# Audio-Beamformer_HMI_V1_0.net
KiCad netlist of a schematic drawn in Altium Designer
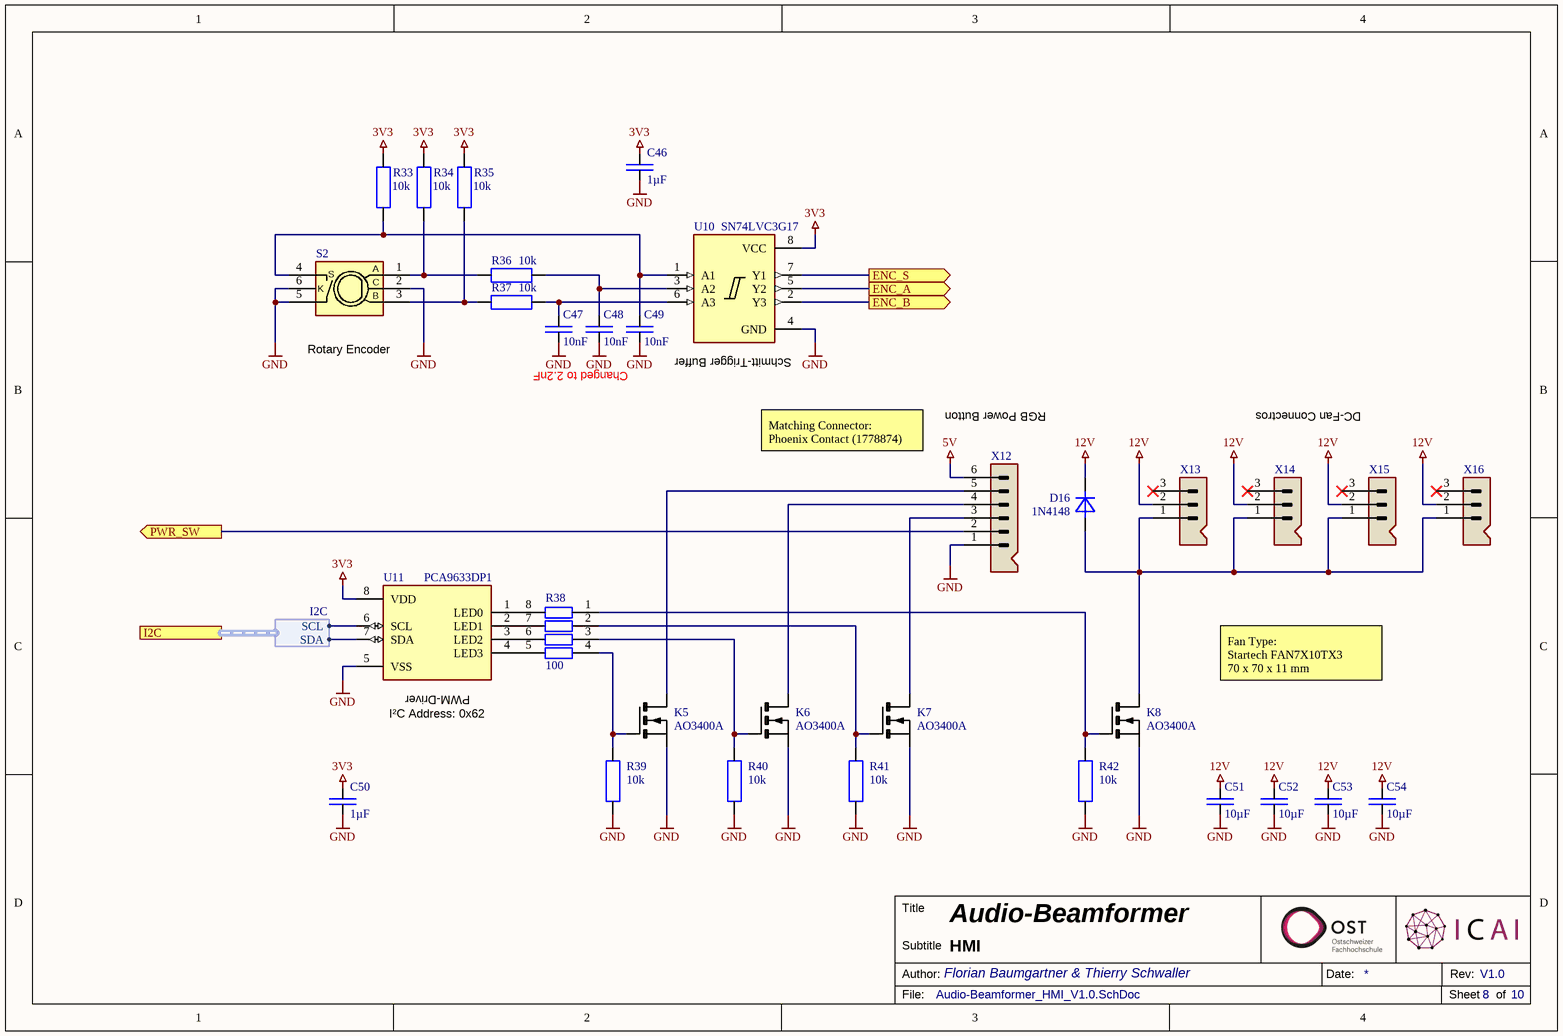
[diagram p0: Audio-Beamformer_HMI_V1.0.SchDoc]

(export (version "E")
  (design (tool "Eeschema 10.0.6"))
  (components
    (comp (ref "C46")
      (value "1µF")
      (footprint "SMD Keramikkondensator 0603")
      (description "CAP-MK")
      (libsource (lib "AudioAmp") (part "C-CAPACITOR"))
    )
    (comp (ref "C47")
      (value "10nF")
      (footprint "SMD Keramikkondensator 0603")
      (description "CAP-MK")
      (libsource (lib "AudioAmp") (part "C-CAPACITOR"))
    )
    (comp (ref "C48")
      (value "10nF")
      (footprint "SMD Keramikkondensator 0603")
      (description "CAP-MK")
      (libsource (lib "AudioAmp") (part "C-CAPACITOR"))
    )
    (comp (ref "C49")
      (value "10nF")
      (footprint "SMD Keramikkondensator 0603")
      (description "CAP-MK")
      (libsource (lib "AudioAmp") (part "C-CAPACITOR"))
    )
    (comp (ref "C50")
      (value "1µF")
      (footprint "SMD Keramikkondensator 0603")
      (description "CAP-MK")
      (libsource (lib "AudioAmp") (part "C-CAPACITOR"))
    )
    (comp (ref "C51")
      (value "10µF")
      (footprint "SMD Keramikkondensator 1206")
      (description "CAP-MK")
      (libsource (lib "AudioAmp") (part "C-CAPACITOR"))
    )
    (comp (ref "C52")
      (value "10µF")
      (footprint "SMD Keramikkondensator 1206")
      (description "CAP-MK")
      (libsource (lib "AudioAmp") (part "C-CAPACITOR"))
    )
    (comp (ref "C53")
      (value "10µF")
      (footprint "SMD Keramikkondensator 1206")
      (description "CAP-MK")
      (libsource (lib "AudioAmp") (part "C-CAPACITOR"))
    )
    (comp (ref "C54")
      (value "10µF")
      (footprint "SMD Keramikkondensator 1206")
      (description "CAP-MK")
      (libsource (lib "AudioAmp") (part "C-CAPACITOR"))
    )
    (comp (ref "D16")
      (value "1N4148")
      (footprint "SMD Diode SOD-123")
      (description "DIODE (alt V)")
      (libsource (lib "TFS Integrated Library") (part "R-DIODE"))
    )
    (comp (ref "K5")
      (value "AO3400A")
      (footprint "SMD MOSFET SOT-23")
      (description "MOSFET N-Channel")
      (libsource (lib "Nixie-Test") (part "K-FET{colon}NIGE"))
    )
    (comp (ref "K6")
      (value "AO3400A")
      (footprint "SMD MOSFET SOT-23")
      (description "MOSFET N-Channel")
      (libsource (lib "Nixie-Test") (part "K-FET{colon}NIGE"))
    )
    (comp (ref "K7")
      (value "AO3400A")
      (footprint "SMD MOSFET SOT-23")
      (description "MOSFET N-Channel")
      (libsource (lib "Nixie-Test") (part "K-FET{colon}NIGE"))
    )
    (comp (ref "K8")
      (value "AO3400A")
      (footprint "SMD MOSFET SOT-23")
      (description "MOSFET N-Channel")
      (libsource (lib "Nixie-Test") (part "K-FET{colon}NIGE"))
    )
    (comp (ref "R33")
      (value "10k")
      (footprint "SMD Widerstand 0603")
      (description "RES (E=Heizwiderstand B=Messwandler)")
      (libsource (lib "") (part "R-RESISTOR_1"))
    )
    (comp (ref "R34")
      (value "10k")
      (footprint "SMD Widerstand 0603")
      (description "RES (E=Heizwiderstand B=Messwandler)")
      (libsource (lib "") (part "R-RESISTOR_1"))
    )
    (comp (ref "R35")
      (value "10k")
      (footprint "SMD Widerstand 0603")
      (description "RES (E=Heizwiderstand B=Messwandler)")
      (libsource (lib "") (part "R-RESISTOR_1"))
    )
    (comp (ref "R36")
      (value "10k")
      (footprint "SMD Widerstand 0603")
      (description "RES (E=Heizwiderstand B=Messwandler)")
      (libsource (lib "TFS Integrated Library") (part "R-RESISTOR"))
    )
    (comp (ref "R37")
      (value "10k")
      (footprint "SMD Widerstand 0603")
      (description "RES (E=Heizwiderstand B=Messwandler)")
      (libsource (lib "TFS Integrated Library") (part "R-RESISTOR"))
    )
    (comp (ref "R38")
      (value "100")
      (footprint "SMD Widerstand Array 4-Fach 0603")
      (description "Isolated Resistor Array")
      (libsource (lib "Fleet-Monitor") (part "R-Array Single Quad E24 - 330"))
    )
    (comp (ref "R39")
      (value "10k")
      (footprint "SMD Widerstand 0603")
      (description "RES (E=Heizwiderstand B=Messwandler)")
      (libsource (lib "") (part "R-RESISTOR_1"))
    )
    (comp (ref "R40")
      (value "10k")
      (footprint "SMD Widerstand 0603")
      (description "RES (E=Heizwiderstand B=Messwandler)")
      (libsource (lib "") (part "R-RESISTOR_1"))
    )
    (comp (ref "R41")
      (value "10k")
      (footprint "SMD Widerstand 0603")
      (description "RES (E=Heizwiderstand B=Messwandler)")
      (libsource (lib "") (part "R-RESISTOR_1"))
    )
    (comp (ref "R42")
      (value "10k")
      (footprint "SMD Widerstand 0603")
      (description "RES (E=Heizwiderstand B=Messwandler)")
      (libsource (lib "") (part "R-RESISTOR_1"))
    )
    (comp (ref "S2")
      (value "PEC11R-4025F-S0024")
      (footprint "THT Rotary Encoder with Switch")
      (description "Rotary Encoder")
      (libsource (lib "Audio-Beamformer") (part "S-Rotary Encoder"))
    )
    (comp (ref "U10")
      (value "SN74LVC3G17")
      (footprint "SMD IC SM-8")
      (description "Tripple Schmitt-Trigger Buffer")
      (libsource (lib "Audio-Beamformer") (part "U-SN74LVC3G17DCTR"))
    )
    (comp (ref "U11")
      (value "PCA9633DP1")
      (footprint "SMD IC TSSOP-8")
      (description "I2C Quad LED-Driver")
      (libsource (lib "Audio-Beamformer") (part "U-PCA9633DP1"))
    )
    (comp (ref "X12")
      (value "Board-To-Wire Connector (Receptacle)")
      (footprint "THT Connector 2.5mm 6-Pol (1778667)")
      (libsource (lib "Audio-Beamformer") (part "X-Stiftleiste (6-Fach)"))
    )
    (comp (ref "X13")
      (value "Stiftleiste (3-Fach)")
      (footprint "THT Connector 2.54mm 3-Pol (61900311021)")
      (libsource (lib "Audio-Beamformer") (part "X-Stiftleiste (3-Fach)"))
    )
    (comp (ref "X14")
      (value "Stiftleiste (3-Fach)")
      (footprint "THT Connector 2.54mm 3-Pol (61900311021)")
      (libsource (lib "Audio-Beamformer") (part "X-Stiftleiste (3-Fach)"))
    )
    (comp (ref "X15")
      (value "Stiftleiste (3-Fach)")
      (footprint "THT Connector 2.54mm 3-Pol (61900311021)")
      (libsource (lib "Audio-Beamformer") (part "X-Stiftleiste (3-Fach)"))
    )
    (comp (ref "X16")
      (value "Stiftleiste (3-Fach)")
      (footprint "THT Connector 2.54mm 3-Pol (61900311021)")
      (libsource (lib "Audio-Beamformer") (part "X-Stiftleiste (3-Fach)"))
    )
  )
  (nets
    (net (code "2") (name "/ENC_A") (class "Default")
      (node (ref "U10") (pin "5") (pinfunction "Y2_5") (pintype "output"))
    )
    (net (code "3") (name "/ENC_B") (class "Default")
      (node (ref "U10") (pin "2") (pinfunction "Y3_2") (pintype "output"))
    )
    (net (code "4") (name "/ENC_S") (class "Default")
      (node (ref "U10") (pin "7") (pinfunction "Y1_7") (pintype "output"))
    )
    (net (code "5") (name "/PWR_SW") (class "Default")
      (node (ref "X12") (pin "2") (pinfunction "2_2") (pintype "passive"))
    )
    (net (code "6") (name "/SCL") (class "Default")
      (node (ref "U11") (pin "6") (pinfunction "SCL_6") (pintype "bidirectional"))
    )
    (net (code "7") (name "/SDA") (class "Default")
      (node (ref "U11") (pin "7") (pinfunction "SDA_7") (pintype "bidirectional"))
    )
    (net (code "9") (name "3V3") (class "Default")
      (node (ref "C46") (pin "2") (pinfunction "2_2") (pintype "passive"))
      (node (ref "C50") (pin "2") (pinfunction "2_2") (pintype "passive"))
      (node (ref "R33") (pin "2") (pinfunction "2_2") (pintype "passive"))
      (node (ref "R34") (pin "2") (pinfunction "2_2") (pintype "passive"))
      (node (ref "R35") (pin "2") (pinfunction "2_2") (pintype "passive"))
      (node (ref "U10") (pin "8") (pinfunction "VCC_8") (pintype "power_in"))
      (node (ref "U11") (pin "8") (pinfunction "VDD_8") (pintype "power_in"))
    )
    (net (code "10") (name "5V") (class "Default")
      (node (ref "X12") (pin "6") (pinfunction "6_6") (pintype "passive"))
    )
    (net (code "11") (name "12V") (class "Default")
      (node (ref "C51") (pin "2") (pinfunction "2_2") (pintype "passive"))
      (node (ref "C52") (pin "2") (pinfunction "2_2") (pintype "passive"))
      (node (ref "C53") (pin "2") (pinfunction "2_2") (pintype "passive"))
      (node (ref "C54") (pin "2") (pinfunction "2_2") (pintype "passive"))
      (node (ref "D16") (pin "K") (pinfunction "K_K") (pintype "passive"))
      (node (ref "X13") (pin "2") (pinfunction "2_2") (pintype "passive"))
      (node (ref "X14") (pin "2") (pinfunction "2_2") (pintype "passive"))
      (node (ref "X15") (pin "2") (pinfunction "2_2") (pintype "passive"))
      (node (ref "X16") (pin "2") (pinfunction "2_2") (pintype "passive"))
    )
    (net (code "12") (name "GND") (class "Default")
      (node (ref "C46") (pin "1") (pinfunction "1_1") (pintype "passive"))
      (node (ref "C47") (pin "1") (pinfunction "1_1") (pintype "passive"))
      (node (ref "C48") (pin "1") (pinfunction "1_1") (pintype "passive"))
      (node (ref "C49") (pin "1") (pinfunction "1_1") (pintype "passive"))
      (node (ref "C50") (pin "1") (pinfunction "1_1") (pintype "passive"))
      (node (ref "C51") (pin "1") (pinfunction "1_1") (pintype "passive"))
      (node (ref "C52") (pin "1") (pinfunction "1_1") (pintype "passive"))
      (node (ref "C53") (pin "1") (pinfunction "1_1") (pintype "passive"))
      (node (ref "C54") (pin "1") (pinfunction "1_1") (pintype "passive"))
      (node (ref "K5") (pin "S") (pinfunction "S_S") (pintype "passive"))
      (node (ref "K6") (pin "S") (pinfunction "S_S") (pintype "passive"))
      (node (ref "K7") (pin "S") (pinfunction "S_S") (pintype "passive"))
      (node (ref "K8") (pin "S") (pinfunction "S_S") (pintype "passive"))
      (node (ref "R39") (pin "1") (pinfunction "1_1") (pintype "passive"))
      (node (ref "R40") (pin "1") (pinfunction "1_1") (pintype "passive"))
      (node (ref "R41") (pin "1") (pinfunction "1_1") (pintype "passive"))
      (node (ref "R42") (pin "1") (pinfunction "1_1") (pintype "passive"))
      (node (ref "S2") (pin "2") (pinfunction "C_2") (pintype "passive"))
      (node (ref "S2") (pin "5") (pinfunction "S_5") (pintype "passive"))
      (node (ref "S2") (pin "6") (pinfunction "K_6") (pintype "passive"))
      (node (ref "U10") (pin "4") (pinfunction "GND_4") (pintype "power_in"))
      (node (ref "U11") (pin "5") (pinfunction "VSS_5") (pintype "power_in"))
      (node (ref "X12") (pin "1") (pinfunction "1_1") (pintype "passive"))
    )
    (net (code "13") (name "Net-(D16-PadA)") (class "Default")
      (node (ref "D16") (pin "A") (pinfunction "A_A") (pintype "passive"))
      (node (ref "K8") (pin "D") (pinfunction "D_D") (pintype "passive"))
      (node (ref "X13") (pin "1") (pinfunction "1_1") (pintype "passive"))
      (node (ref "X14") (pin "1") (pinfunction "1_1") (pintype "passive"))
      (node (ref "X15") (pin "1") (pinfunction "1_1") (pintype "passive"))
      (node (ref "X16") (pin "1") (pinfunction "1_1") (pintype "passive"))
    )
    (net (code "14") (name "Net-(K5-PadD)") (class "Default")
      (node (ref "K5") (pin "D") (pinfunction "D_D") (pintype "passive"))
      (node (ref "X12") (pin "5") (pinfunction "5_5") (pintype "passive"))
    )
    (net (code "15") (name "Net-(K5-PadG)") (class "Default")
      (node (ref "K5") (pin "G") (pinfunction "G_G") (pintype "passive"))
      (node (ref "R38") (pin "4") (pinfunction "4_4") (pintype "passive"))
      (node (ref "R39") (pin "2") (pinfunction "2_2") (pintype "passive"))
    )
    (net (code "16") (name "Net-(K6-PadD)") (class "Default")
      (node (ref "K6") (pin "D") (pinfunction "D_D") (pintype "passive"))
      (node (ref "X12") (pin "4") (pinfunction "4_4") (pintype "passive"))
    )
    (net (code "17") (name "Net-(K6-PadG)") (class "Default")
      (node (ref "K6") (pin "G") (pinfunction "G_G") (pintype "passive"))
      (node (ref "R38") (pin "3") (pinfunction "3_3") (pintype "passive"))
      (node (ref "R40") (pin "2") (pinfunction "2_2") (pintype "passive"))
    )
    (net (code "18") (name "Net-(K7-PadD)") (class "Default")
      (node (ref "K7") (pin "D") (pinfunction "D_D") (pintype "passive"))
      (node (ref "X12") (pin "3") (pinfunction "3_3") (pintype "passive"))
    )
    (net (code "19") (name "Net-(K7-PadG)") (class "Default")
      (node (ref "K7") (pin "G") (pinfunction "G_G") (pintype "passive"))
      (node (ref "R38") (pin "2") (pinfunction "2_2") (pintype "passive"))
      (node (ref "R41") (pin "2") (pinfunction "2_2") (pintype "passive"))
    )
    (net (code "20") (name "Net-(K8-PadG)") (class "Default")
      (node (ref "K8") (pin "G") (pinfunction "G_G") (pintype "passive"))
      (node (ref "R38") (pin "1") (pinfunction "1_1") (pintype "passive"))
      (node (ref "R42") (pin "2") (pinfunction "2_2") (pintype "passive"))
    )
    (net (code "21") (name "Net-(S2-A)") (class "Default")
      (node (ref "R34") (pin "1") (pinfunction "1_1") (pintype "passive"))
      (node (ref "R36") (pin "2") (pinfunction "2_2") (pintype "passive"))
      (node (ref "S2") (pin "1") (pinfunction "A_1") (pintype "passive"))
    )
    (net (code "22") (name "Net-(S2-B)") (class "Default")
      (node (ref "R35") (pin "1") (pinfunction "1_1") (pintype "passive"))
      (node (ref "R37") (pin "2") (pinfunction "2_2") (pintype "passive"))
      (node (ref "S2") (pin "3") (pinfunction "B_3") (pintype "passive"))
    )
    (net (code "23") (name "Net-(U10-A1)") (class "Default")
      (node (ref "C49") (pin "2") (pinfunction "2_2") (pintype "passive"))
      (node (ref "R33") (pin "1") (pinfunction "1_1") (pintype "passive"))
      (node (ref "S2") (pin "4") (pinfunction "S_4") (pintype "passive"))
      (node (ref "U10") (pin "1") (pinfunction "A1_1") (pintype "input"))
    )
    (net (code "24") (name "Net-(U10-A2)") (class "Default")
      (node (ref "C48") (pin "2") (pinfunction "2_2") (pintype "passive"))
      (node (ref "R36") (pin "1") (pinfunction "1_1") (pintype "passive"))
      (node (ref "U10") (pin "3") (pinfunction "A2_3") (pintype "input"))
    )
    (net (code "25") (name "Net-(U10-A3)") (class "Default")
      (node (ref "C47") (pin "2") (pinfunction "2_2") (pintype "passive"))
      (node (ref "R37") (pin "1") (pinfunction "1_1") (pintype "passive"))
      (node (ref "U10") (pin "6") (pinfunction "A3_6") (pintype "input"))
    )
    (net (code "26") (name "Net-(U11-LED0)") (class "Default")
      (node (ref "R38") (pin "8") (pinfunction "8_8") (pintype "passive"))
      (node (ref "U11") (pin "1") (pinfunction "LED0_1") (pintype "passive"))
    )
    (net (code "27") (name "Net-(U11-LED1)") (class "Default")
      (node (ref "R38") (pin "7") (pinfunction "7_7") (pintype "passive"))
      (node (ref "U11") (pin "2") (pinfunction "LED1_2") (pintype "passive"))
    )
    (net (code "28") (name "Net-(U11-LED2)") (class "Default")
      (node (ref "R38") (pin "6") (pinfunction "6_6") (pintype "passive"))
      (node (ref "U11") (pin "3") (pinfunction "LED2_3") (pintype "passive"))
    )
    (net (code "29") (name "Net-(U11-LED3)") (class "Default")
      (node (ref "R38") (pin "5") (pinfunction "5_5") (pintype "passive"))
      (node (ref "U11") (pin "4") (pinfunction "LED3_4") (pintype "passive"))
    )
    (net (code "30") (name "unconnected-(X13-Pad3)") (class "Default")
      (node (ref "X13") (pin "3") (pinfunction "3_3") (pintype "passive+no_connect"))
    )
    (net (code "31") (name "unconnected-(X14-Pad3)") (class "Default")
      (node (ref "X14") (pin "3") (pinfunction "3_3") (pintype "passive+no_connect"))
    )
    (net (code "32") (name "unconnected-(X15-Pad3)") (class "Default")
      (node (ref "X15") (pin "3") (pinfunction "3_3") (pintype "passive+no_connect"))
    )
    (net (code "33") (name "unconnected-(X16-Pad3)") (class "Default")
      (node (ref "X16") (pin "3") (pinfunction "3_3") (pintype "passive+no_connect"))
    )
  )
)
